# BufferBiasAmp.net
KiCad netlist of a schematic drawn in Altium Designer
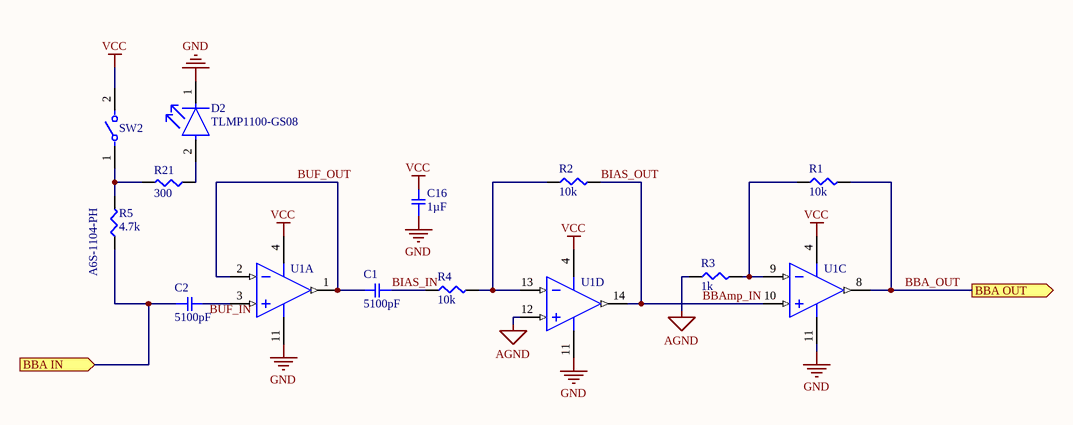
[diagram p0: BufferBiasAmp.SchDoc]

(export (version "E")
  (design (tool "Eeschema 10.0.6"))
  (components
    (comp (ref "C1")
      (value "5100pF")
      (footprint "SMD-0603C")
      (description "CAP CER 5100PF 50V U2J 0603")
      (fields
        (field (name "MANUFACTURER") "Murata Electronics North America")
        (field (name "MANUFACTURER PART NUMBER") "GRM1887U1H512JA01D")
      )
      (libsource (lib "capacitor_murata_0603") (part "GRM1887U1H512JA01D"))
    )
    (comp (ref "C2")
      (value "5100pF")
      (footprint "SMD-0603C")
      (description "CAP CER 5100PF 50V U2J 0603")
      (fields
        (field (name "DIGI-KEY PART NUMBER") "490-6399-1-ND")
        (field (name "PART NUMBER") "GRM1887U1H512JA01D")
      )
      (libsource (lib "capacitor_murata_0603") (part "GRM1887U1H512JA01D"))
    )
    (comp (ref "C16")
      (value "1µF")
      (footprint "SMD-0603C")
      (description "CAP CER 1UF 16V X7R 0603")
      (fields
        (field (name "MANUFACTURER") "Samsung Electro-Mechanics")
        (field (name "MANUFACTURER PART NUMBER") "CL10A105KA8NNNC")
      )
      (libsource (lib "capacitor_murata_0603") (part "GCM188R71C105KA64D"))
    )
    (comp (ref "D2")
      (value "TLMP1100-GS08")
      (footprint "FP-6_541-5056_01-4-MFG")
      (description "Green 561nm LED Indication - Discrete 2.1V 0603 (1608 Metric)")
      (fields (field (name "MANUFACTURER") "Vishay"))
      (libsource (lib "Altium Content Vault") (part "8706943c75ba83719d021d2fdc84c58"))
    )
    (comp (ref "R1")
      (value "10k")
      (footprint "SMD-0603-RES")
      (description "RES SMD 10K OHM 1% 1/10W 0603")
      (fields
        (field (name "MANUFACTURER") "Panasonic Electronic Components")
        (field (name "MANUFACTURER PART NUMBER") "RNCP0603FTD10K0")
      )
      (libsource (lib "Panasonic_resistor_0603") (part "ERJ-3EKF1002V"))
    )
    (comp (ref "R2")
      (value "10k")
      (footprint "SMD-0603-RES")
      (description "RES SMD 10K OHM 1% 1/10W 0603")
      (fields
        (field (name "MANUFACTURER") "Panasonic Electronic Components")
        (field (name "MANUFACTURER PART NUMBER") "RNCP0603FTD10K0")
      )
      (libsource (lib "Panasonic_resistor_0603") (part "ERJ-3EKF1002V"))
    )
    (comp (ref "R3")
      (value "1k")
      (footprint "SMD-0603-RES")
      (description "RES SMD 1K OHM 1% 1/10W 0603")
      (fields
        (field (name "MANUFACTURER") "Stackpole Electronics Inc")
        (field (name "MANUFACTURER PART NUMBER") "RNCP0603FTD1K00")
      )
      (libsource (lib "Panasonic_resistor_0603") (part "ERJ-3EKF1001V"))
    )
    (comp (ref "R4")
      (value "10k")
      (footprint "SMD-0603-RES")
      (description "RES SMD 10K OHM 1% 1/10W 0603")
      (fields
        (field (name "MANUFACTURER") "Panasonic Electronic Components")
        (field (name "MANUFACTURER PART NUMBER") "RNCP0603FTD10K0")
      )
      (libsource (lib "Panasonic_resistor_0603") (part "ERJ-3EKF1002V"))
    )
    (comp (ref "R5")
      (value "4.7k")
      (footprint "SMD-0603-RES")
      (description "RES SMD 4.7K OHM 1% 1/10W 0603")
      (fields
        (field (name "MANUFACTURER") "Panasonic Electronic Components")
        (field (name "MANUFACTURER PART NUMBER") "ERJ-3EKF4701V")
      )
      (libsource (lib "Panasonic_resistor_0603") (part "ERJ-3EKF4701V"))
    )
    (comp (ref "R21")
      (value "300")
      (footprint "SMD-0603-RES")
      (description "RES SMD 300 OHM 1% 1/10W 0603")
      (fields
        (field (name "MANUFACTURER") "Panasonic Electronic Components")
        (field (name "MANUFACTURER PART NUMBER") "ERJ-3EKF3000V")
      )
      (libsource (lib "Panasonic_resistor_0603") (part "ERJ-3EKF3000V"))
    )
    (comp (ref "SW2")
      (value "Switch_Omron_A6S-1104-PH_eec")
      (footprint "Omron_A6S-1104-PH_0")
      (description "SWITCH SLIDE DIP SPST 25MA 24V")
      (fields (field (name "PART NUMBER") "A6S-1104-PH") (field (name "VOLTAGE") "24V"))
      (libsource (lib "Switch_Omron_A6S-1104-PH_eec") (part "Switch_Omron_A6S-1104-PH_eec"))
    )
    (comp (ref "U1")
      (value "OPA1604AIPWR")
      (footprint "PW0014A_N")
      (fields (field (name "MANUFACTURER") "Texas Instruments"))
      (libsource (lib "Altium Content Vault") (part "TI-OPA16X4_4XXX-14"))
    )
  )
  (nets
    (net (code "1") (name "/BBA IN") (class "Default")
      (node (ref "C2") (pin "1") (pinfunction "1_1") (pintype "passive"))
      (node (ref "R5") (pin "1") (pinfunction "1_1") (pintype "passive"))
    )
    (net (code "2") (name "/BBA_OUT") (class "Default")
      (node (ref "R1") (pin "2") (pinfunction "2_2") (pintype "passive"))
      (node (ref "U1") (pin "8") (pinfunction "OUT_C_8") (pintype "output"))
    )
    (net (code "3") (name "/BBAmp_IN") (class "Default")
      (node (ref "R2") (pin "2") (pinfunction "2_2") (pintype "passive"))
      (node (ref "U1") (pin "10") (pinfunction "IN_C+_10") (pintype "input"))
      (node (ref "U1") (pin "14") (pinfunction "OUT_D_14") (pintype "output"))
    )
    (net (code "4") (name "/BIAS_IN") (class "Default")
      (node (ref "C1") (pin "1") (pinfunction "1_1") (pintype "passive"))
      (node (ref "R4") (pin "1") (pinfunction "1_1") (pintype "passive"))
    )
    (net (code "6") (name "/BUF_OUT") (class "Default")
      (node (ref "C1") (pin "2") (pinfunction "2_2") (pintype "passive"))
      (node (ref "U1") (pin "1") (pinfunction "OUT_A_1") (pintype "output"))
      (node (ref "U1") (pin "2") (pinfunction "IN_A-_2") (pintype "input"))
    )
    (net (code "7") (name "AGND") (class "Default")
      (node (ref "R3") (pin "1") (pinfunction "1_1") (pintype "passive"))
      (node (ref "U1") (pin "12") (pinfunction "IN_D+_12") (pintype "input"))
    )
    (net (code "8") (name "GND") (class "Default")
      (node (ref "C16") (pin "1") (pinfunction "1_1") (pintype "passive"))
      (node (ref "D2") (pin "1") (pinfunction "C_1") (pintype "passive"))
      (node (ref "U1") (pin "11") (pinfunction "V-_11") (pintype "power_in"))
    )
    (net (code "9") (name "Net-(D2-A)") (class "Default")
      (node (ref "D2") (pin "2") (pinfunction "A_2") (pintype "passive"))
      (node (ref "R21") (pin "1") (pinfunction "1_1") (pintype "passive"))
    )
    (net (code "10") (name "Net-(R21-Pad2)") (class "Default")
      (node (ref "R21") (pin "2") (pinfunction "2_2") (pintype "passive"))
      (node (ref "R5") (pin "2") (pinfunction "2_2") (pintype "passive"))
      (node (ref "SW2") (pin "1") (pinfunction "1_1") (pintype "passive"))
    )
    (net (code "11") (name "Net-(U1A-IN_A+)") (class "Default")
      (node (ref "C2") (pin "2") (pinfunction "2_2") (pintype "passive"))
      (node (ref "U1") (pin "3") (pinfunction "IN_A+_3") (pintype "input"))
    )
    (net (code "12") (name "Net-(U1C-IN_C-)") (class "Default")
      (node (ref "R1") (pin "1") (pinfunction "1_1") (pintype "passive"))
      (node (ref "R3") (pin "2") (pinfunction "2_2") (pintype "passive"))
      (node (ref "U1") (pin "9") (pinfunction "IN_C-_9") (pintype "input"))
    )
    (net (code "13") (name "Net-(U1D-IN_D-)") (class "Default")
      (node (ref "R2") (pin "1") (pinfunction "1_1") (pintype "passive"))
      (node (ref "R4") (pin "2") (pinfunction "2_2") (pintype "passive"))
      (node (ref "U1") (pin "13") (pinfunction "IN_D-_13") (pintype "input"))
    )
    (net (code "14") (name "VCC") (class "Default")
      (node (ref "C16") (pin "2") (pinfunction "2_2") (pintype "passive"))
      (node (ref "SW2") (pin "2") (pinfunction "2_2") (pintype "passive"))
      (node (ref "U1") (pin "4") (pinfunction "V+_4") (pintype "power_in"))
    )
  )
)
